# RS232Board.net
KiCad netlist of a schematic drawn in EAGLE
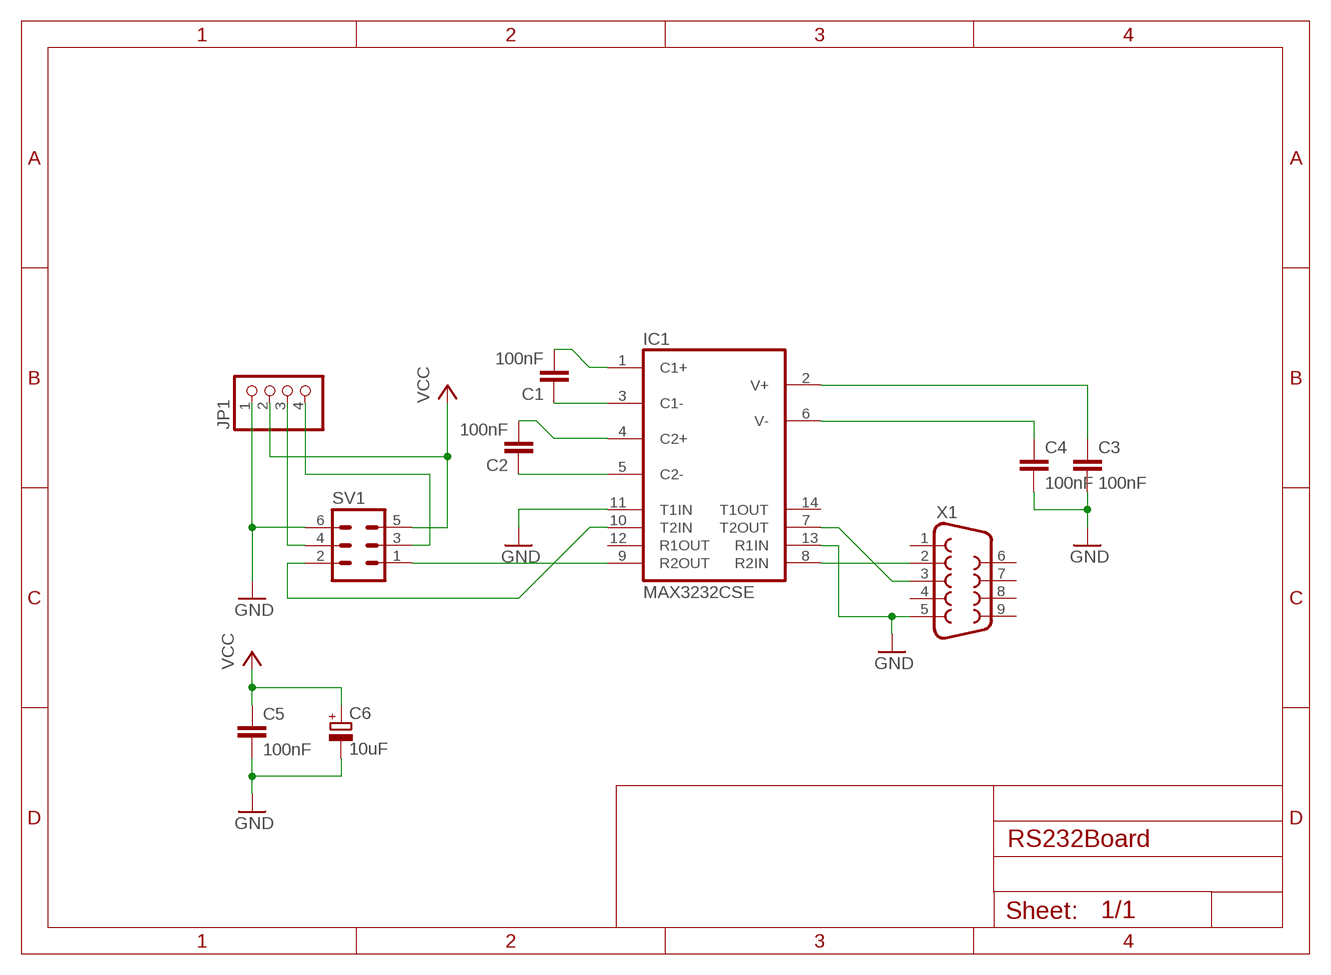
[diagram p0: schematic, sheet 1]

(export (version "E")
  (design (tool "Eeschema 10.0.6"))
  (components
    (comp (ref "C1")
      (value "100nF")
      (footprint "eagle-import:C1206")
      (libsource (lib "eagle-import") (part "C-EUC1206"))
    )
    (comp (ref "C2")
      (value "100nF")
      (footprint "eagle-import:C1206")
      (libsource (lib "eagle-import") (part "C-EUC1206"))
    )
    (comp (ref "C3")
      (value "100nF")
      (footprint "eagle-import:C1206")
      (libsource (lib "eagle-import") (part "C-EUC1206"))
    )
    (comp (ref "C4")
      (value "100nF")
      (footprint "eagle-import:C1206")
      (libsource (lib "eagle-import") (part "C-EUC1206"))
    )
    (comp (ref "C5")
      (value "100nF")
      (footprint "eagle-import:C1206")
      (libsource (lib "eagle-import") (part "C-EUC1206"))
    )
    (comp (ref "C6")
      (value "10uF")
      (footprint "eagle-import:SMC_C")
      (libsource (lib "eagle-import") (part "CPOL-EUSMCC"))
    )
    (comp (ref "IC1")
      (value "MAX3232CSE")
      (footprint "eagle-import:SO16")
      (libsource (lib "eagle-import") (part "MAX3232SEC"))
    )
    (comp (ref "JP1")
      (value "PINHD-1X4")
      (footprint "eagle-import:1X04")
      (libsource (lib "eagle-import") (part "PINHD-1X4"))
    )
    (comp (ref "SV1")
      (value "ML6")
      (footprint "eagle-import:ML6")
      (libsource (lib "eagle-import") (part "ML6"))
    )
    (comp (ref "X1")
      (value "F09HP")
      (footprint "eagle-import:F09HP")
      (libsource (lib "eagle-import") (part "F09HP"))
    )
  )
  (nets
    (net (code "1") (name "GND") (class "Default")
      (node (ref "C3") (pin "2") (pinfunction "2_2") (pintype "passive"))
      (node (ref "C4") (pin "2") (pinfunction "2_2") (pintype "passive"))
      (node (ref "C5") (pin "2") (pinfunction "2_2") (pintype "passive"))
      (node (ref "C6") (pin "-") (pinfunction "-_-") (pintype "passive"))
      (node (ref "IC1") (pin "11") (pinfunction "T1IN_11") (pintype "input"))
      (node (ref "IC1") (pin "13") (pinfunction "R1IN_13") (pintype "input"))
      (node (ref "JP1") (pin "1") (pinfunction "1_1") (pintype "passive"))
      (node (ref "SV1") (pin "6") (pinfunction "6_6") (pintype "passive"))
      (node (ref "X1") (pin "5") (pinfunction "5_5") (pintype "passive"))
    )
    (net (code "2") (name "Net-(IC1A-C1+)") (class "Default")
      (node (ref "C1") (pin "2") (pinfunction "2_2") (pintype "passive"))
      (node (ref "IC1") (pin "1") (pinfunction "C1+_1") (pintype "bidirectional"))
    )
    (net (code "3") (name "Net-(IC1A-C1-)") (class "Default")
      (node (ref "C1") (pin "1") (pinfunction "1_1") (pintype "passive"))
      (node (ref "IC1") (pin "3") (pinfunction "C1-_3") (pintype "bidirectional"))
    )
    (net (code "4") (name "Net-(IC1A-C2+)") (class "Default")
      (node (ref "C2") (pin "2") (pinfunction "2_2") (pintype "passive"))
      (node (ref "IC1") (pin "4") (pinfunction "C2+_4") (pintype "bidirectional"))
    )
    (net (code "5") (name "Net-(IC1A-C2-)") (class "Default")
      (node (ref "C2") (pin "1") (pinfunction "1_1") (pintype "passive"))
      (node (ref "IC1") (pin "5") (pinfunction "C2-_5") (pintype "bidirectional"))
    )
    (net (code "6") (name "Net-(IC1A-R2IN)") (class "Default")
      (node (ref "IC1") (pin "8") (pinfunction "R2IN_8") (pintype "input"))
      (node (ref "X1") (pin "2") (pinfunction "2_2") (pintype "passive"))
    )
    (net (code "7") (name "Net-(IC1A-R2OUT)") (class "Default")
      (node (ref "IC1") (pin "9") (pinfunction "R2OUT_9") (pintype "output"))
      (node (ref "SV1") (pin "1") (pinfunction "1_1") (pintype "passive"))
    )
    (net (code "8") (name "Net-(IC1A-T2IN)") (class "Default")
      (node (ref "IC1") (pin "10") (pinfunction "T2IN_10") (pintype "input"))
      (node (ref "SV1") (pin "2") (pinfunction "2_2") (pintype "passive"))
    )
    (net (code "9") (name "Net-(IC1A-T2OUT)") (class "Default")
      (node (ref "IC1") (pin "7") (pinfunction "T2OUT_7") (pintype "output"))
      (node (ref "X1") (pin "3") (pinfunction "3_3") (pintype "passive"))
    )
    (net (code "10") (name "Net-(IC1A-V+)") (class "Default")
      (node (ref "C3") (pin "1") (pinfunction "1_1") (pintype "passive"))
      (node (ref "IC1") (pin "2") (pinfunction "V+_2") (pintype "bidirectional"))
    )
    (net (code "11") (name "Net-(IC1A-V-)") (class "Default")
      (node (ref "C4") (pin "1") (pinfunction "1_1") (pintype "passive"))
      (node (ref "IC1") (pin "6") (pinfunction "V-_6") (pintype "bidirectional"))
    )
    (net (code "12") (name "Net-(JP1-Pad3)") (class "Default")
      (node (ref "JP1") (pin "3") (pinfunction "3_3") (pintype "passive"))
      (node (ref "SV1") (pin "4") (pinfunction "4_4") (pintype "passive"))
    )
    (net (code "13") (name "Net-(JP1-Pad4)") (class "Default")
      (node (ref "JP1") (pin "4") (pinfunction "4_4") (pintype "passive"))
      (node (ref "SV1") (pin "3") (pinfunction "3_3") (pintype "passive"))
    )
    (net (code "14") (name "VCC") (class "Default")
      (node (ref "C5") (pin "1") (pinfunction "1_1") (pintype "passive"))
      (node (ref "C6") (pin "+") (pinfunction "+_+") (pintype "passive"))
      (node (ref "JP1") (pin "2") (pinfunction "2_2") (pintype "passive"))
      (node (ref "SV1") (pin "5") (pinfunction "5_5") (pintype "passive"))
    )
    (net (code "15") (name "unconnected-(IC1A-R1OUT-Pad12)") (class "Default")
      (node (ref "IC1") (pin "12") (pinfunction "R1OUT_12") (pintype "output"))
    )
    (net (code "16") (name "unconnected-(IC1A-T1OUT-Pad14)") (class "Default")
      (node (ref "IC1") (pin "14") (pinfunction "T1OUT_14") (pintype "output"))
    )
    (net (code "17") (name "unconnected-(X1-Pad1)") (class "Default")
      (node (ref "X1") (pin "1") (pinfunction "1_1") (pintype "passive"))
    )
    (net (code "18") (name "unconnected-(X1-Pad4)") (class "Default")
      (node (ref "X1") (pin "4") (pinfunction "4_4") (pintype "passive"))
    )
    (net (code "19") (name "unconnected-(X1-Pad6)") (class "Default")
      (node (ref "X1") (pin "6") (pinfunction "6_6") (pintype "passive"))
    )
    (net (code "20") (name "unconnected-(X1-Pad7)") (class "Default")
      (node (ref "X1") (pin "7") (pinfunction "7_7") (pintype "passive"))
    )
    (net (code "21") (name "unconnected-(X1-Pad8)") (class "Default")
      (node (ref "X1") (pin "8") (pinfunction "8_8") (pintype "passive"))
    )
    (net (code "22") (name "unconnected-(X1-Pad9)") (class "Default")
      (node (ref "X1") (pin "9") (pinfunction "9_9") (pintype "passive"))
    )
  )
)
